# Skayboard.net
KiCad netlist of a schematic drawn in Altium Designer
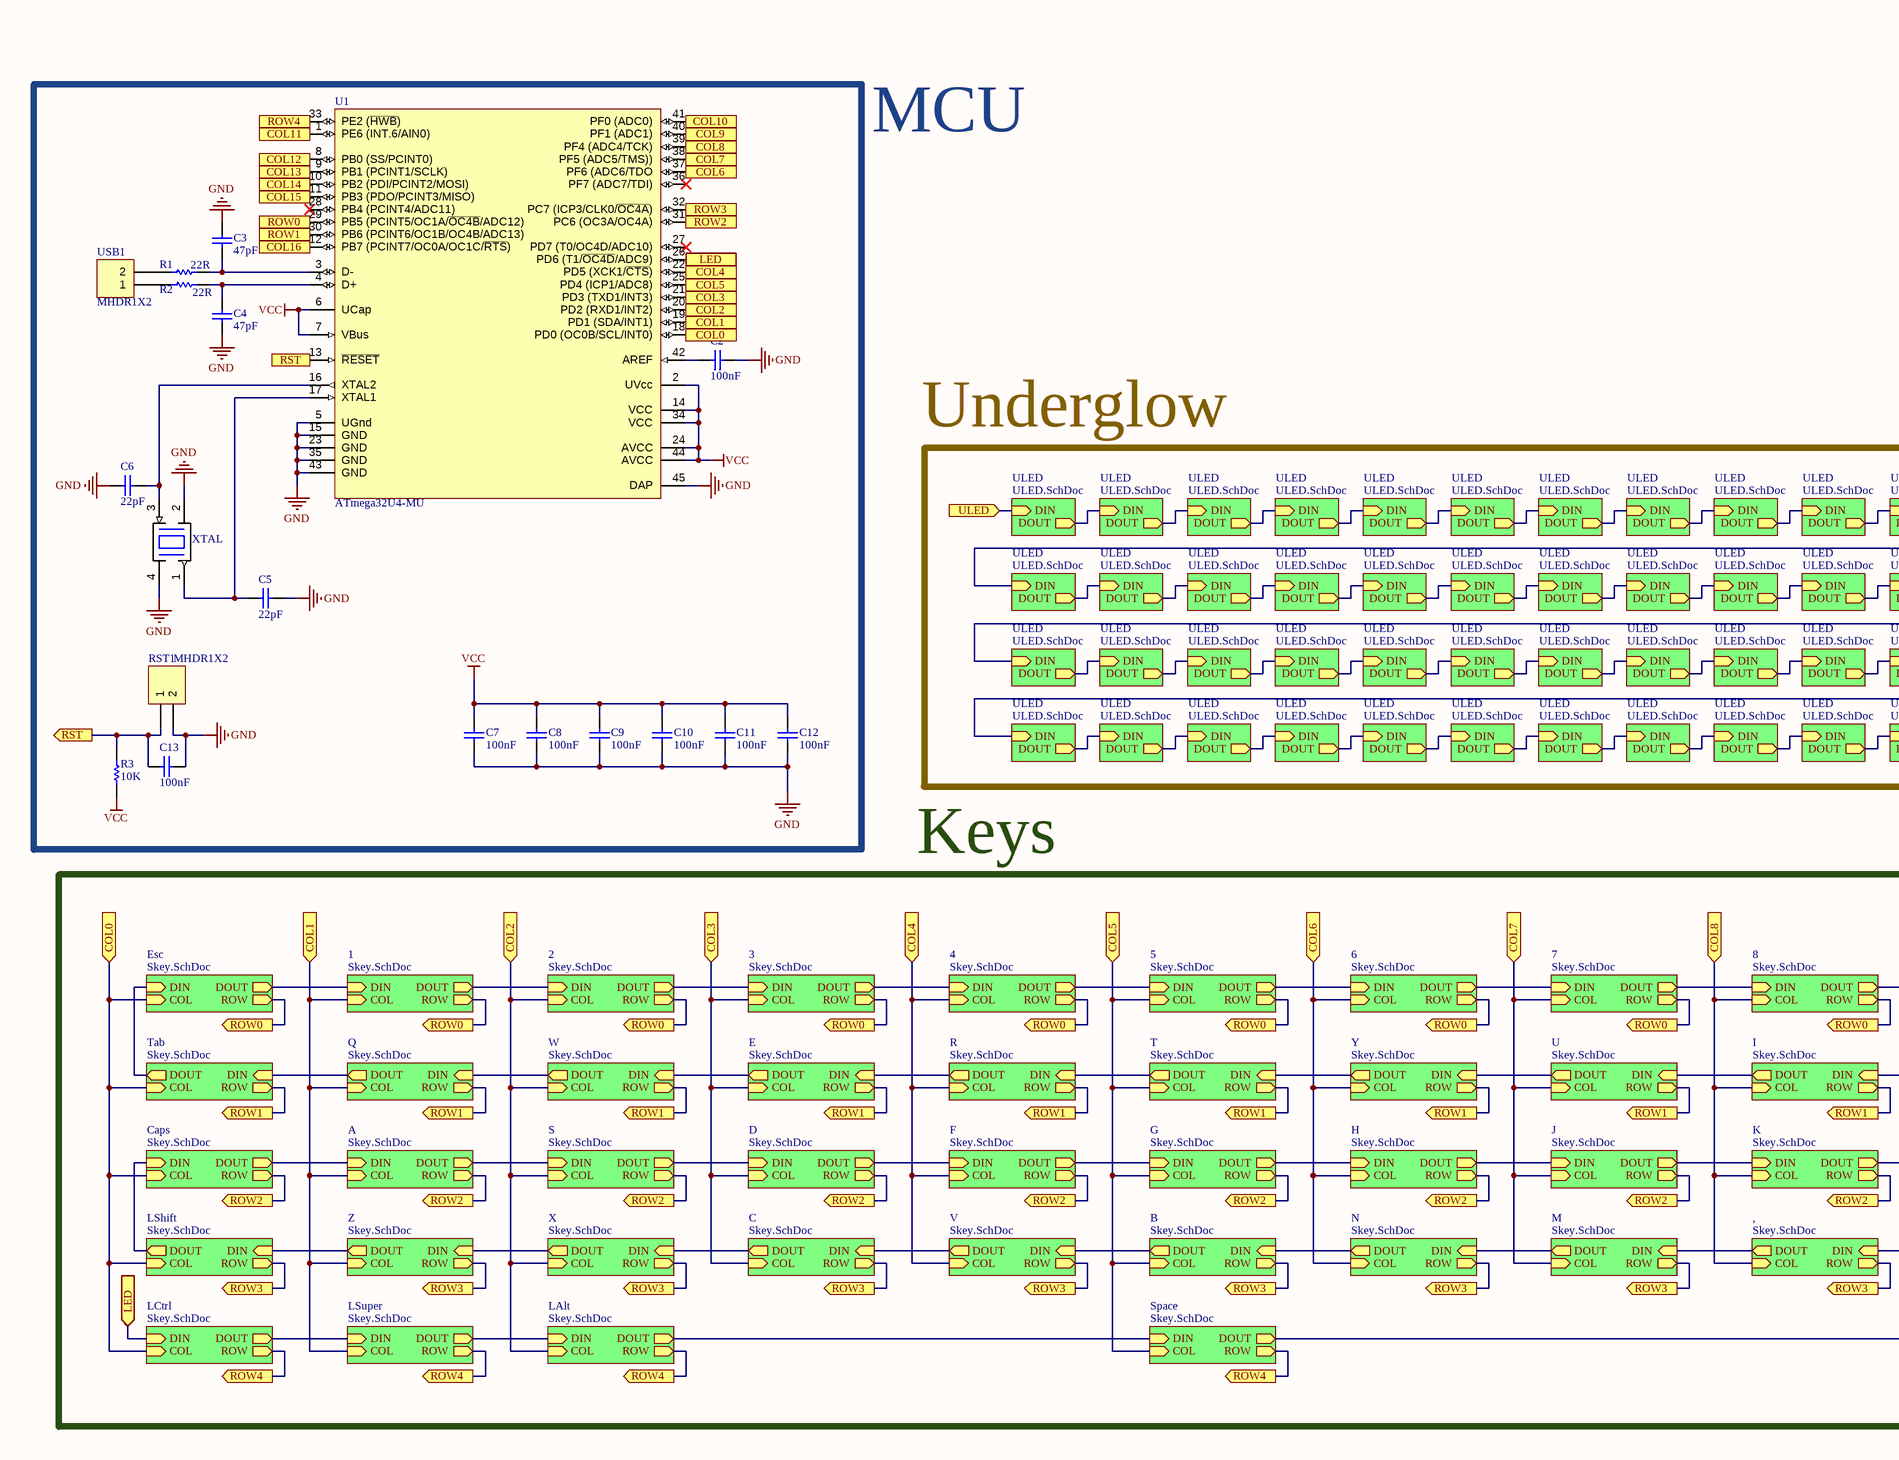
[diagram p0: Skayboard.SchDoc, left]
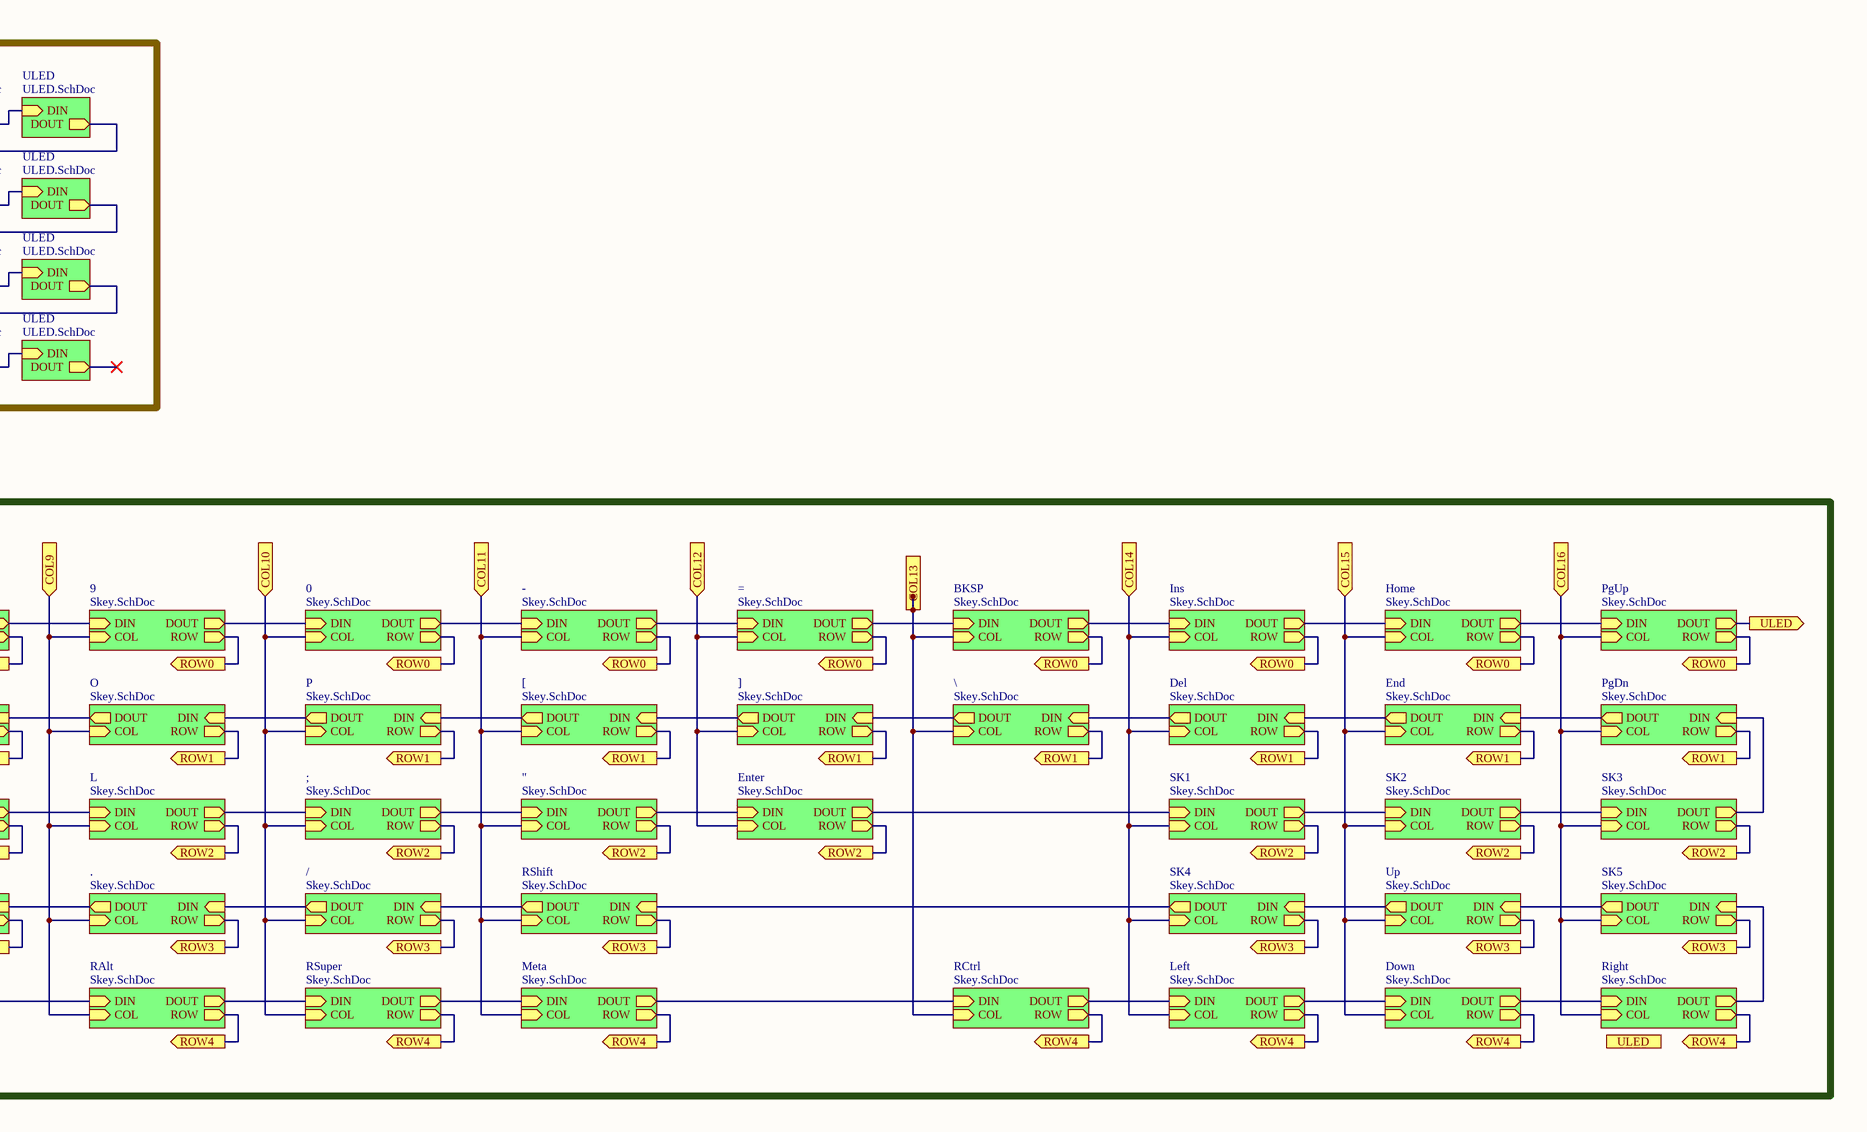
[diagram p1: Skayboard.SchDoc, right]

(export (version "E")
  (design (tool "Eeschema 10.0.6"))
  (components
    (comp (ref "C2")
      (value "100nF")
      (footprint "CAPC1005X55X30LL05T10")
      (fields (field (name "MANUFACTURER") "Kemet") (field (name "PART NUMBER") "C0402C104K4RACTU"))
      (libsource (lib "Altium Content Vault") (part "CAP"))
    )
    (comp (ref "C3")
      (value "47pF")
      (footprint "CAPC1005X55X25LL05T10")
      (fields (field (name "PART NUMBER") "GRM1555C1H470JA01D") (field (name "MANUFACTURER") "Murata"))
      (libsource (lib "Altium Content Vault") (part "CAP"))
    )
    (comp (ref "C4")
      (value "47pF")
      (footprint "CAPC1005X55X25LL05T10")
      (fields (field (name "PART NUMBER") "GRM1555C1H470JA01D") (field (name "MANUFACTURER") "Murata"))
      (libsource (lib "Altium Content Vault") (part "CAP"))
    )
    (comp (ref "C5")
      (value "22pF")
      (footprint "CAPC1005X56X25NL10T15")
      (fields
        (field (name "PART NUMBER") "04025A220JAT2A")
        (field (name "MANUFACTURER") "AVX Interconnect / Elco")
      )
      (libsource (lib "Altium Content Vault") (part "CAP"))
    )
    (comp (ref "C6")
      (value "22pF")
      (footprint "CAPC1005X56X25NL10T15")
      (fields
        (field (name "PART NUMBER") "04025A220JAT2A")
        (field (name "MANUFACTURER") "AVX Interconnect / Elco")
      )
      (libsource (lib "Altium Content Vault") (part "CAP"))
    )
    (comp (ref "C7")
      (value "100nF")
      (footprint "CAPC1005X55X30LL05T10")
      (fields (field (name "MANUFACTURER") "Kemet") (field (name "PART NUMBER") "C0402C104K4RACTU"))
      (libsource (lib "Altium Content Vault") (part "CAP"))
    )
    (comp (ref "C8")
      (value "100nF")
      (footprint "CAPC1005X55X30LL05T10")
      (fields (field (name "MANUFACTURER") "Kemet") (field (name "PART NUMBER") "C0402C104K4RACTU"))
      (libsource (lib "Altium Content Vault") (part "CAP"))
    )
    (comp (ref "C9")
      (value "100nF")
      (footprint "CAPC1005X55X30LL05T10")
      (fields (field (name "MANUFACTURER") "Kemet") (field (name "PART NUMBER") "C0402C104K4RACTU"))
      (libsource (lib "Altium Content Vault") (part "CAP"))
    )
    (comp (ref "C10")
      (value "100nF")
      (footprint "CAPC1005X55X30LL05T10")
      (fields (field (name "MANUFACTURER") "Kemet") (field (name "PART NUMBER") "C0402C104K4RACTU"))
      (libsource (lib "Altium Content Vault") (part "CAP"))
    )
    (comp (ref "C11")
      (value "100nF")
      (footprint "CAPC1005X55X30LL05T10")
      (fields (field (name "MANUFACTURER") "Kemet") (field (name "PART NUMBER") "C0402C104K4RACTU"))
      (libsource (lib "Altium Content Vault") (part "CAP"))
    )
    (comp (ref "C12")
      (value "100nF")
      (footprint "CAPC1005X55X30LL05T10")
      (fields (field (name "MANUFACTURER") "Kemet") (field (name "PART NUMBER") "C0402C104K4RACTU"))
      (libsource (lib "Altium Content Vault") (part "CAP"))
    )
    (comp (ref "C13")
      (value "100nF")
      (footprint "CAPC1005X55X30LL05T10")
      (fields (field (name "MANUFACTURER") "Kemet") (field (name "PART NUMBER") "C0402C104K4RACTU"))
      (libsource (lib "Altium Content Vault") (part "CAP"))
    )
    (comp (ref "R1")
      (value "22R")
      (footprint "RESC1005X40X25LL05T05")
      (description "22")
      (fields (field (name "MANUFACTURER") "Vishay Dale") (field (name "PART NUMBER") "CRCW040222R0FKED"))
      (libsource (lib "Altium Content Vault") (part "RES"))
    )
    (comp (ref "R2")
      (value "22R")
      (footprint "RESC1005X40X25LL05T05")
      (description "22")
      (fields (field (name "MANUFACTURER") "Vishay Dale") (field (name "PART NUMBER") "CRCW040222R0FKED"))
      (libsource (lib "Altium Content Vault") (part "RES"))
    )
    (comp (ref "R3")
      (value "10K")
      (footprint "RESC1005X40X25NL05T05")
      (fields (field (name "PART NUMBER") "ERT-J0ER103J") (field (name "MANUFACTURER") "Panasonic"))
      (libsource (lib "Altium Content Vault") (part "RES"))
    )
    (comp (ref "RST1")
      (value "MHDR1X2")
      (footprint "MHDR1X2")
      (description "Header, 2-Pin")
      (fields (field (name "PUBLISHER") "Altium Limited"))
      (libsource (lib "Miscellaneous Connectors") (part "MHDR1X2"))
    )
    (comp (ref "U1")
      (value "ATmega32U4-MU")
      (footprint "44PW_M")
      (libsource (lib "Altium Content Vault") (part "MC-8B-ATM16U4-SQ45"))
    )
    (comp (ref "USB1")
      (value "MHDR1X2")
      (footprint "MHDR1X2")
      (description "Header, 2-Pin")
      (fields (field (name "PUBLISHER") "Altium Limited"))
      (libsource (lib "") (part "MHDR1X2_1"))
    )
    (comp (ref "XTAL")
      (value "16MCR")
      (footprint "XTAL16M")
      (description "16Mhz crystal resonator, JLCPCB #C13738")
      (libsource (lib "Skayboard") (part "16MCR"))
    )
  )
  (nets
    (net (code "1") (name "/COL0") (class "Default")
      (node (ref "U1") (pin "18") (pinfunction "PD0_(OC0B/SCL/INT0)_18") (pintype "bidirectional"))
    )
    (net (code "2") (name "/COL1") (class "Default")
      (node (ref "U1") (pin "19") (pinfunction "PD1_(SDA/INT1)_19") (pintype "bidirectional"))
    )
    (net (code "3") (name "/COL2") (class "Default")
      (node (ref "U1") (pin "20") (pinfunction "PD2_(RXD1/INT2)_20") (pintype "bidirectional"))
    )
    (net (code "4") (name "/COL3") (class "Default")
      (node (ref "U1") (pin "21") (pinfunction "PD3_(TXD1/INT3)_21") (pintype "bidirectional"))
    )
    (net (code "5") (name "/COL4") (class "Default")
      (node (ref "U1") (pin "22") (pinfunction "PD5_(XCK1/~{CTS})_22") (pintype "bidirectional"))
    )
    (net (code "6") (name "/COL5") (class "Default")
      (node (ref "U1") (pin "25") (pinfunction "PD4_(ICP1/ADC8)_25") (pintype "bidirectional"))
    )
    (net (code "7") (name "/COL6") (class "Default")
      (node (ref "U1") (pin "37") (pinfunction "PF6_(ADC6/TDO_37") (pintype "bidirectional"))
    )
    (net (code "8") (name "/COL7") (class "Default")
      (node (ref "U1") (pin "38") (pinfunction "PF5_(ADC5/TMS))_38") (pintype "bidirectional"))
    )
    (net (code "9") (name "/COL8") (class "Default")
      (node (ref "U1") (pin "39") (pinfunction "PF4_(ADC4/TCK)_39") (pintype "bidirectional"))
    )
    (net (code "10") (name "/COL9") (class "Default")
      (node (ref "U1") (pin "40") (pinfunction "PF1_(ADC1)_40") (pintype "bidirectional"))
    )
    (net (code "11") (name "/COL10") (class "Default")
      (node (ref "U1") (pin "41") (pinfunction "PF0_(ADC0)_41") (pintype "bidirectional"))
    )
    (net (code "12") (name "/COL11") (class "Default")
      (node (ref "U1") (pin "1") (pinfunction "PE6_(INT.6/AIN0)_1") (pintype "bidirectional"))
    )
    (net (code "13") (name "/COL12") (class "Default")
      (node (ref "U1") (pin "8") (pinfunction "PB0_(SS/PCINT0)_8") (pintype "bidirectional"))
    )
    (net (code "14") (name "/COL13") (class "Default")
      (node (ref "U1") (pin "9") (pinfunction "PB1_(PCINT1/SCLK)_9") (pintype "bidirectional"))
    )
    (net (code "15") (name "/COL14") (class "Default")
      (node (ref "U1") (pin "10") (pinfunction "PB2_(PDI/PCINT2/MOSI)_10") (pintype "bidirectional"))
    )
    (net (code "16") (name "/COL15") (class "Default")
      (node (ref "U1") (pin "11") (pinfunction "PB3_(PDO/PCINT3/MISO)_11") (pintype "bidirectional"))
    )
    (net (code "17") (name "/COL16") (class "Default")
      (node (ref "U1") (pin "12") (pinfunction "PB7_(PCINT7/OC0A/OC1C/~{RTS})_12") (pintype "bidirectional"))
    )
    (net (code "137") (name "/LED") (class "Default")
      (node (ref "U1") (pin "26") (pinfunction "PD6_(T1/~{OC4D}/ADC9)_26") (pintype "bidirectional"))
    )
    (net (code "138") (name "/ROW0") (class "Default")
      (node (ref "U1") (pin "29") (pinfunction "PB5_(PCINT5/OC1A/~{OC4B}/ADC12)_29") (pintype "bidirectional"))
    )
    (net (code "139") (name "/ROW1") (class "Default")
      (node (ref "U1") (pin "30") (pinfunction "PB6_(PCINT6/OC1B/OC4B/ADC13)_30") (pintype "bidirectional"))
    )
    (net (code "140") (name "/ROW2") (class "Default")
      (node (ref "U1") (pin "31") (pinfunction "PC6_(OC3A/OC4A)_31") (pintype "bidirectional"))
    )
    (net (code "141") (name "/ROW3") (class "Default")
      (node (ref "U1") (pin "32") (pinfunction "PC7_(ICP3/CLK0/~{OC4A})_32") (pintype "bidirectional"))
    )
    (net (code "142") (name "/ROW4") (class "Default")
      (node (ref "U1") (pin "33") (pinfunction "PE2_(~{HWB})_33") (pintype "bidirectional"))
    )
    (net (code "143") (name "/RST") (class "Default")
      (node (ref "C13") (pin "2") (pinfunction "2_2") (pintype "passive"))
      (node (ref "R3") (pin "2") (pinfunction "2_2") (pintype "passive"))
      (node (ref "RST1") (pin "1") (pinfunction "1_1") (pintype "passive"))
      (node (ref "U1") (pin "13") (pinfunction "~{RESET}_13") (pintype "input"))
    )
    (net (code "145") (name "GND") (class "Default")
      (node (ref "C10") (pin "1") (pinfunction "1_1") (pintype "passive"))
      (node (ref "C11") (pin "1") (pinfunction "1_1") (pintype "passive"))
      (node (ref "C12") (pin "1") (pinfunction "1_1") (pintype "passive"))
      (node (ref "C13") (pin "1") (pinfunction "1_1") (pintype "passive"))
      (node (ref "C2") (pin "2") (pinfunction "2_2") (pintype "passive"))
      (node (ref "C3") (pin "2") (pinfunction "2_2") (pintype "passive"))
      (node (ref "C4") (pin "1") (pinfunction "1_1") (pintype "passive"))
      (node (ref "C5") (pin "1") (pinfunction "1_1") (pintype "passive"))
      (node (ref "C6") (pin "1") (pinfunction "1_1") (pintype "passive"))
      (node (ref "C7") (pin "1") (pinfunction "1_1") (pintype "passive"))
      (node (ref "C8") (pin "1") (pinfunction "1_1") (pintype "passive"))
      (node (ref "C9") (pin "1") (pinfunction "1_1") (pintype "passive"))
      (node (ref "RST1") (pin "2") (pinfunction "2_2") (pintype "passive"))
      (node (ref "U1") (pin "15") (pinfunction "GND_15") (pintype "power_in"))
      (node (ref "U1") (pin "23") (pinfunction "GND_23") (pintype "power_in"))
      (node (ref "U1") (pin "35") (pinfunction "GND_35") (pintype "power_in"))
      (node (ref "U1") (pin "43") (pinfunction "GND_43") (pintype "power_in"))
      (node (ref "U1") (pin "45") (pinfunction "DAP_45") (pintype "power_in"))
      (node (ref "U1") (pin "5") (pinfunction "UGnd_5") (pintype "power_in"))
      (node (ref "XTAL") (pin "2") (pintype "power_in"))
      (node (ref "XTAL") (pin "4") (pintype "power_in"))
    )
    (net (code "146") (name "Net-(R1-Pad2)") (class "Default")
      (node (ref "R1") (pin "2") (pinfunction "2_2") (pintype "passive"))
      (node (ref "USB1") (pin "2") (pinfunction "2_2") (pintype "passive"))
    )
    (net (code "147") (name "Net-(R2-Pad2)") (class "Default")
      (node (ref "R2") (pin "2") (pinfunction "2_2") (pintype "passive"))
      (node (ref "USB1") (pin "1") (pinfunction "1_1") (pintype "passive"))
    )
    (net (code "148") (name "Net-(U1-AREF)") (class "Default")
      (node (ref "C2") (pin "1") (pinfunction "1_1") (pintype "passive"))
      (node (ref "U1") (pin "42") (pinfunction "AREF_42") (pintype "input"))
    )
    (net (code "149") (name "Net-(U1-D+)") (class "Default")
      (node (ref "C4") (pin "2") (pinfunction "2_2") (pintype "passive"))
      (node (ref "R2") (pin "1") (pinfunction "1_1") (pintype "passive"))
      (node (ref "U1") (pin "4") (pinfunction "D+_4") (pintype "bidirectional"))
    )
    (net (code "150") (name "Net-(U1-D-)") (class "Default")
      (node (ref "C3") (pin "1") (pinfunction "1_1") (pintype "passive"))
      (node (ref "R1") (pin "1") (pinfunction "1_1") (pintype "passive"))
      (node (ref "U1") (pin "3") (pinfunction "D-_3") (pintype "bidirectional"))
    )
    (net (code "151") (name "Net-(U1-XTAL1)") (class "Default")
      (node (ref "C5") (pin "2") (pinfunction "2_2") (pintype "passive"))
      (node (ref "U1") (pin "17") (pinfunction "XTAL1_17") (pintype "input"))
      (node (ref "XTAL") (pin "1") (pintype "output"))
    )
    (net (code "152") (name "Net-(U1-XTAL2)") (class "Default")
      (node (ref "C6") (pin "2") (pinfunction "2_2") (pintype "passive"))
      (node (ref "U1") (pin "16") (pinfunction "XTAL2_16") (pintype "output"))
      (node (ref "XTAL") (pin "3") (pintype "input"))
    )
    (net (code "153") (name "VCC") (class "Default")
      (node (ref "C10") (pin "2") (pinfunction "2_2") (pintype "passive"))
      (node (ref "C11") (pin "2") (pinfunction "2_2") (pintype "passive"))
      (node (ref "C12") (pin "2") (pinfunction "2_2") (pintype "passive"))
      (node (ref "C7") (pin "2") (pinfunction "2_2") (pintype "passive"))
      (node (ref "C8") (pin "2") (pinfunction "2_2") (pintype "passive"))
      (node (ref "C9") (pin "2") (pinfunction "2_2") (pintype "passive"))
      (node (ref "R3") (pin "1") (pinfunction "1_1") (pintype "passive"))
      (node (ref "U1") (pin "14") (pinfunction "VCC_14") (pintype "power_in"))
      (node (ref "U1") (pin "2") (pinfunction "UVcc_2") (pintype "power_in"))
      (node (ref "U1") (pin "24") (pinfunction "AVCC_24") (pintype "power_in"))
      (node (ref "U1") (pin "34") (pinfunction "VCC_34") (pintype "power_in"))
      (node (ref "U1") (pin "44") (pinfunction "AVCC_44") (pintype "power_in"))
      (node (ref "U1") (pin "6") (pinfunction "UCap_6") (pintype "passive"))
      (node (ref "U1") (pin "7") (pinfunction "VBus_7") (pintype "input"))
    )
    (net (code "154") (name "unconnected-(U1-PB4_(PCINT4{slash}ADC11)-Pad28)") (class "Default")
      (node (ref "U1") (pin "28") (pinfunction "PB4_(PCINT4/ADC11)_28") (pintype "bidirectional+no_connect"))
    )
    (net (code "155") (name "unconnected-(U1-PD7_(T0{slash}OC4D{slash}ADC10)-Pad27)") (class "Default")
      (node (ref "U1") (pin "27") (pinfunction "PD7_(T0/OC4D/ADC10)_27") (pintype "bidirectional+no_connect"))
    )
    (net (code "156") (name "unconnected-(U1-PF7_(ADC7{slash}TDI)-Pad36)") (class "Default")
      (node (ref "U1") (pin "36") (pinfunction "PF7_(ADC7/TDI)_36") (pintype "bidirectional+no_connect"))
    )
  )
)
